# Codec.net
KiCad netlist of a schematic drawn in Altium Designer
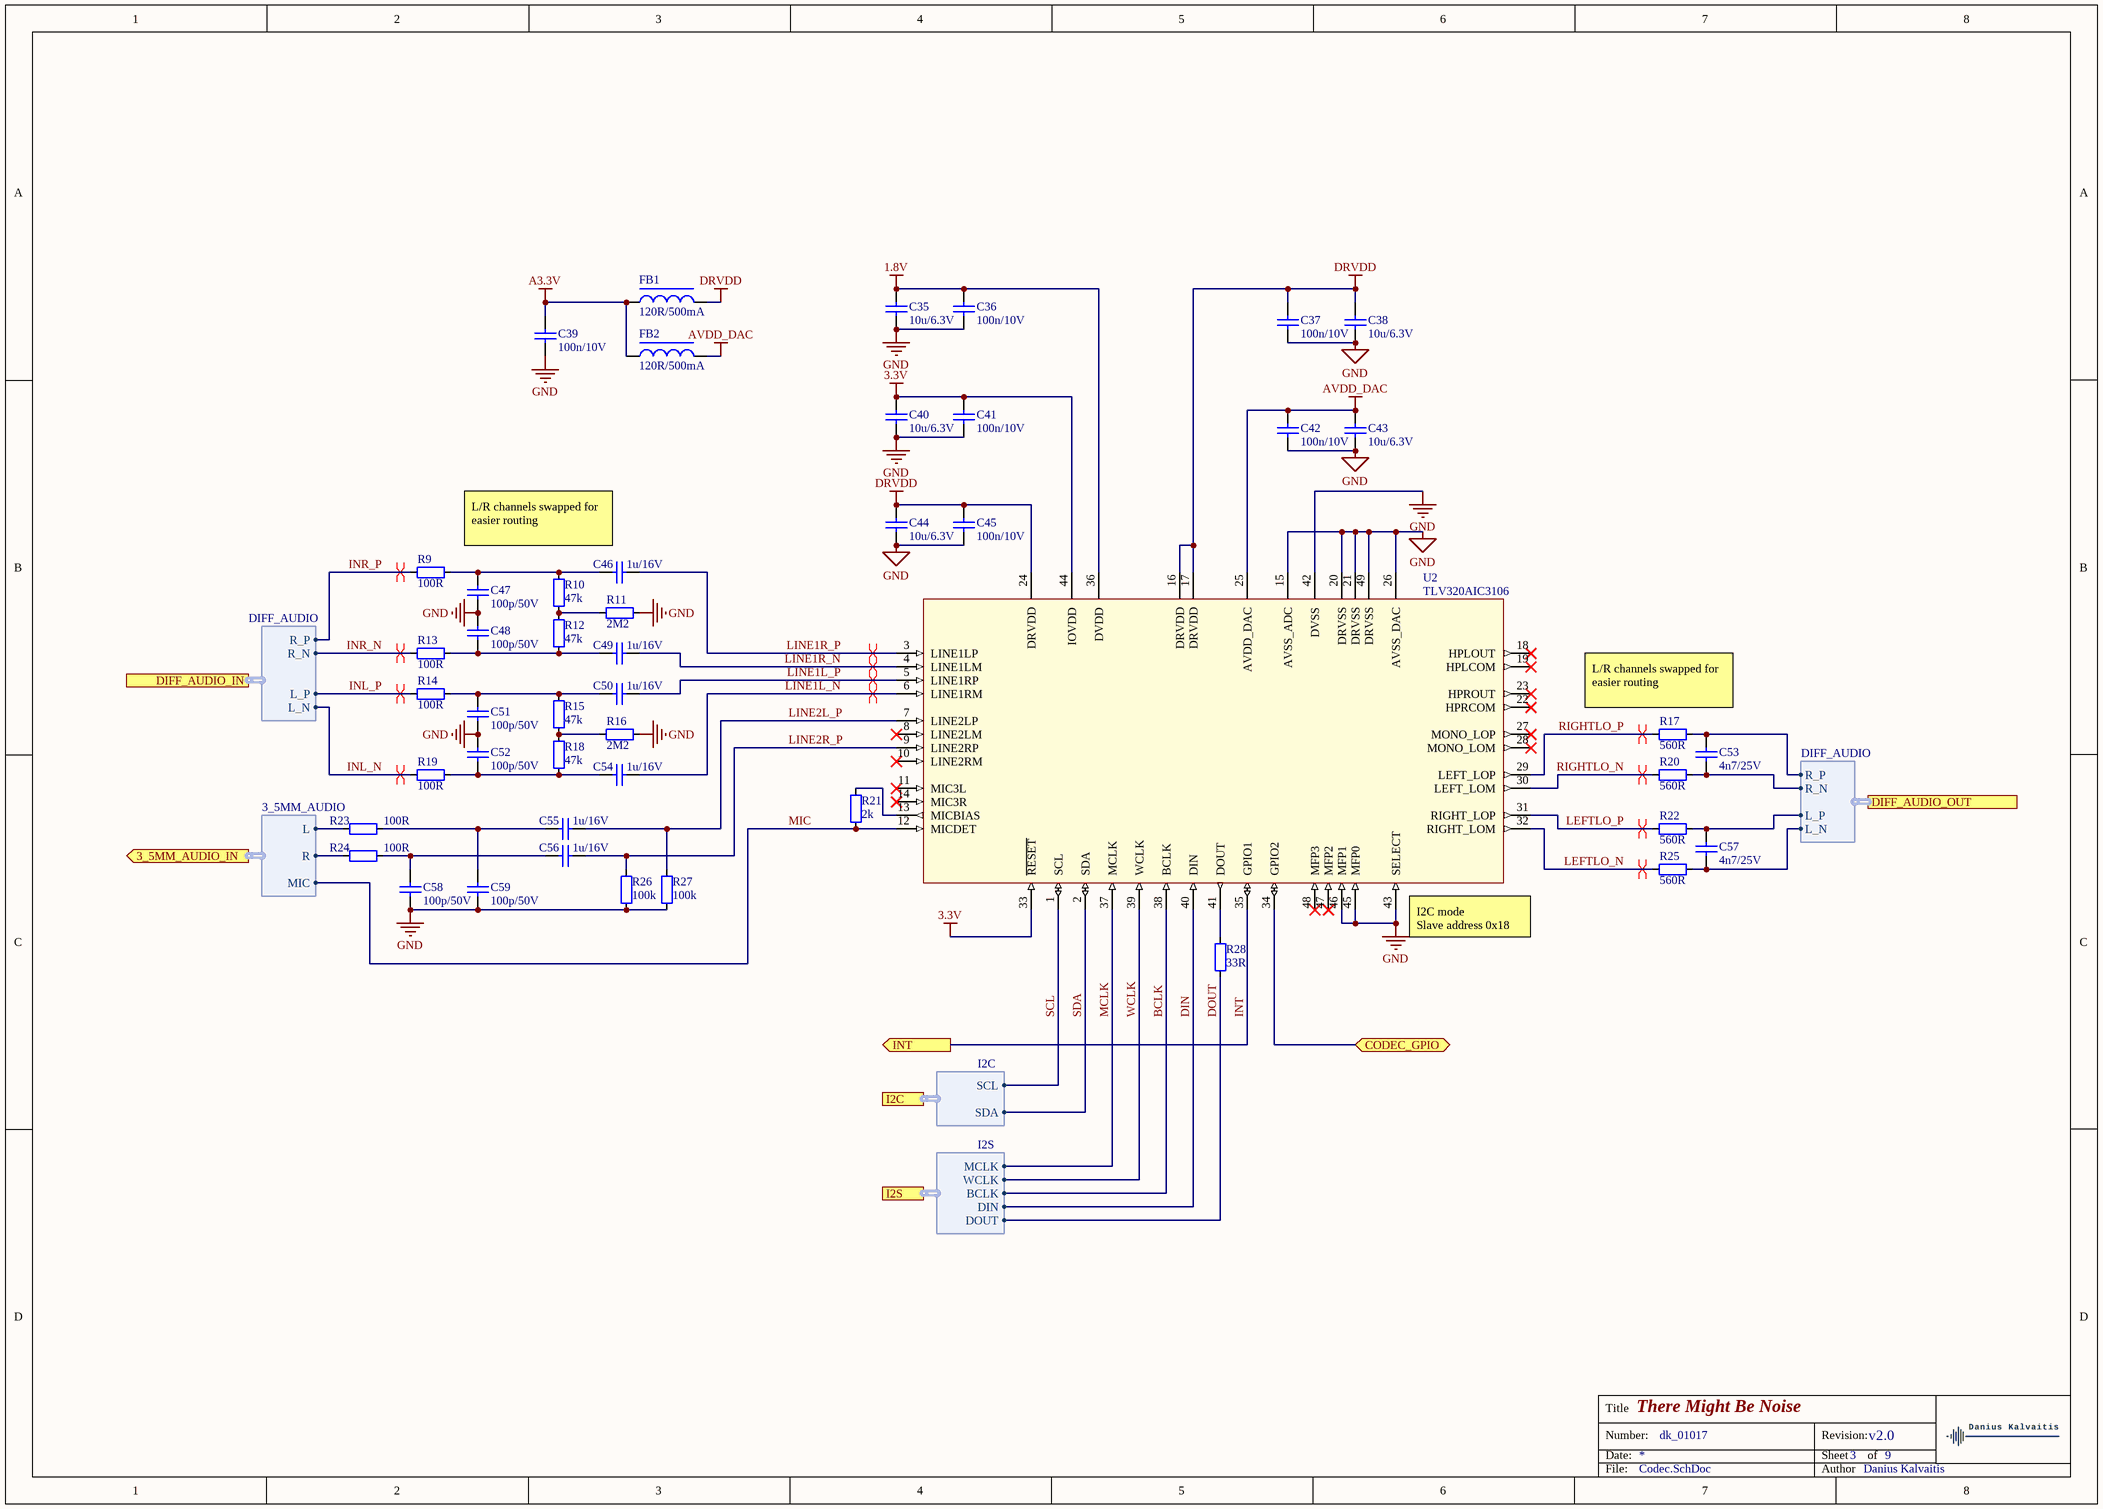
[diagram p0: Codec.SchDoc]

(export (version "E")
  (design (tool "Eeschema 10.0.6"))
  (components
    (comp (ref "C35")
      (value "10u/6.3V")
      (footprint "C0805")
      (fields (field (name "VOLTAGE") "6.3V") (field (name "TOLERANCE") "10%"))
      (libsource (lib "dk_capacitors") (part "10u 6V3 X7R 0805"))
    )
    (comp (ref "C36")
      (value "100n/10V")
      (footprint "C0402")
      (fields (field (name "VOLTAGE") "10V") (field (name "TOLERANCE") "20%"))
      (libsource (lib "dk_capacitors") (part "100n 10V X5R 0402"))
    )
    (comp (ref "C37")
      (value "100n/10V")
      (footprint "C0402")
      (fields (field (name "VOLTAGE") "10V") (field (name "TOLERANCE") "20%"))
      (libsource (lib "dk_capacitors") (part "100n 10V X5R 0402"))
    )
    (comp (ref "C38")
      (value "10u/6.3V")
      (footprint "C0805")
      (fields (field (name "VOLTAGE") "6.3V") (field (name "TOLERANCE") "10%"))
      (libsource (lib "dk_capacitors") (part "10u 6V3 X7R 0805"))
    )
    (comp (ref "C39")
      (value "100n/10V")
      (footprint "C0402")
      (fields (field (name "VOLTAGE") "10V") (field (name "TOLERANCE") "20%"))
      (libsource (lib "dk_capacitors") (part "100n 10V X5R 0402"))
    )
    (comp (ref "C40")
      (value "10u/6.3V")
      (footprint "C0805")
      (fields (field (name "VOLTAGE") "6.3V") (field (name "TOLERANCE") "10%"))
      (libsource (lib "dk_capacitors") (part "10u 6V3 X7R 0805"))
    )
    (comp (ref "C41")
      (value "100n/10V")
      (footprint "C0402")
      (fields (field (name "VOLTAGE") "10V") (field (name "TOLERANCE") "20%"))
      (libsource (lib "dk_capacitors") (part "100n 10V X5R 0402"))
    )
    (comp (ref "C42")
      (value "100n/10V")
      (footprint "C0402")
      (fields (field (name "VOLTAGE") "10V") (field (name "TOLERANCE") "20%"))
      (libsource (lib "dk_capacitors") (part "100n 10V X5R 0402"))
    )
    (comp (ref "C43")
      (value "10u/6.3V")
      (footprint "C0805")
      (fields (field (name "VOLTAGE") "6.3V") (field (name "TOLERANCE") "10%"))
      (libsource (lib "dk_capacitors") (part "10u 6V3 X7R 0805"))
    )
    (comp (ref "C44")
      (value "10u/6.3V")
      (footprint "C0805")
      (fields (field (name "VOLTAGE") "6.3V") (field (name "TOLERANCE") "10%"))
      (libsource (lib "dk_capacitors") (part "10u 6V3 X7R 0805"))
    )
    (comp (ref "C45")
      (value "100n/10V")
      (footprint "C0402")
      (fields (field (name "VOLTAGE") "10V") (field (name "TOLERANCE") "20%"))
      (libsource (lib "dk_capacitors") (part "100n 10V X5R 0402"))
    )
    (comp (ref "C46")
      (value "1u/16V")
      (footprint "C0603")
      (fields (field (name "VOLTAGE") "16V") (field (name "TOLERANCE") "10%"))
      (libsource (lib "dk_capacitors") (part "1u 16V X7R 0603"))
    )
    (comp (ref "C47")
      (value "100p/50V")
      (footprint "C0402")
      (fields (field (name "VOLTAGE") "50V") (field (name "TOLERANCE") "10%"))
      (libsource (lib "dk_capacitors") (part "100p 50V C0G 0402"))
    )
    (comp (ref "C48")
      (value "100p/50V")
      (footprint "C0402")
      (fields (field (name "VOLTAGE") "50V") (field (name "TOLERANCE") "10%"))
      (libsource (lib "dk_capacitors") (part "100p 50V C0G 0402"))
    )
    (comp (ref "C49")
      (value "1u/16V")
      (footprint "C0603")
      (fields (field (name "VOLTAGE") "16V") (field (name "TOLERANCE") "10%"))
      (libsource (lib "dk_capacitors") (part "1u 16V X7R 0603"))
    )
    (comp (ref "C50")
      (value "1u/16V")
      (footprint "C0603")
      (fields (field (name "VOLTAGE") "16V") (field (name "TOLERANCE") "10%"))
      (libsource (lib "dk_capacitors") (part "1u 16V X7R 0603"))
    )
    (comp (ref "C51")
      (value "100p/50V")
      (footprint "C0402")
      (fields (field (name "VOLTAGE") "50V") (field (name "TOLERANCE") "10%"))
      (libsource (lib "dk_capacitors") (part "100p 50V C0G 0402"))
    )
    (comp (ref "C52")
      (value "100p/50V")
      (footprint "C0402")
      (fields (field (name "VOLTAGE") "50V") (field (name "TOLERANCE") "10%"))
      (libsource (lib "dk_capacitors") (part "100p 50V C0G 0402"))
    )
    (comp (ref "C53")
      (value "4n7/25V")
      (footprint "C0402")
      (fields (field (name "VOLTAGE") "25V") (field (name "TOLERANCE") "10%"))
      (libsource (lib "dk_capacitors") (part "4n7 25V X7R 0402"))
    )
    (comp (ref "C54")
      (value "1u/16V")
      (footprint "C0603")
      (fields (field (name "VOLTAGE") "16V") (field (name "TOLERANCE") "10%"))
      (libsource (lib "dk_capacitors") (part "1u 16V X7R 0603"))
    )
    (comp (ref "C55")
      (value "1u/16V")
      (footprint "C0603")
      (fields (field (name "VOLTAGE") "16V") (field (name "TOLERANCE") "10%"))
      (libsource (lib "dk_capacitors") (part "1u 16V X7R 0603"))
    )
    (comp (ref "C56")
      (value "1u/16V")
      (footprint "C0603")
      (fields (field (name "VOLTAGE") "16V") (field (name "TOLERANCE") "10%"))
      (libsource (lib "dk_capacitors") (part "1u 16V X7R 0603"))
    )
    (comp (ref "C57")
      (value "4n7/25V")
      (footprint "C0402")
      (fields (field (name "VOLTAGE") "25V") (field (name "TOLERANCE") "10%"))
      (libsource (lib "dk_capacitors") (part "4n7 25V X7R 0402"))
    )
    (comp (ref "C58")
      (value "100p/50V")
      (footprint "C0402")
      (fields (field (name "VOLTAGE") "50V") (field (name "TOLERANCE") "10%"))
      (libsource (lib "dk_capacitors") (part "100p 50V C0G 0402"))
    )
    (comp (ref "C59")
      (value "100p/50V")
      (footprint "C0402")
      (fields (field (name "VOLTAGE") "50V") (field (name "TOLERANCE") "10%"))
      (libsource (lib "dk_capacitors") (part "100p 50V C0G 0402"))
    )
    (comp (ref "FB1")
      (value "120R/500mA")
      (footprint "FB0402")
      (description "120 Ohms @ 100MHz 1  Ferrite Bead 0402 (1005 Metric) 550mA 190mOhm")
      (fields (field (name "MANUFACTURER PART NUMBER") "BLM15AG121SN1D") (field (name "TOLERANCE") "25%"))
      (libsource (lib "dk_inductors") (part "BLM15AG121SN1D"))
    )
    (comp (ref "FB2")
      (value "120R/500mA")
      (footprint "FB0402")
      (description "120 Ohms @ 100MHz 1  Ferrite Bead 0402 (1005 Metric) 550mA 190mOhm")
      (fields (field (name "MANUFACTURER PART NUMBER") "BLM15AG121SN1D") (field (name "TOLERANCE") "25%"))
      (libsource (lib "dk_inductors") (part "BLM15AG121SN1D"))
    )
    (comp (ref "R9")
      (value "100R")
      (footprint "R0402")
      (fields (field (name "TOLERANCE") "1%") (field (name "VOLTAGE") "50V"))
      (libsource (lib "dk_resistors") (part "100R 63mW 50V 0402"))
    )
    (comp (ref "R10")
      (value "47k")
      (footprint "R0402")
      (fields (field (name "TOLERANCE") "1%") (field (name "VOLTAGE") "50V"))
      (libsource (lib "dk_resistors") (part "47k 63mW 50V 0402"))
    )
    (comp (ref "R11")
      (value "2M2")
      (footprint "R0402")
      (fields (field (name "TOLERANCE") "1%") (field (name "VOLTAGE") "50V"))
      (libsource (lib "dk_resistors") (part "2M2 63mW 50V 0402"))
    )
    (comp (ref "R12")
      (value "47k")
      (footprint "R0402")
      (fields (field (name "TOLERANCE") "1%") (field (name "VOLTAGE") "50V"))
      (libsource (lib "dk_resistors") (part "47k 63mW 50V 0402"))
    )
    (comp (ref "R13")
      (value "100R")
      (footprint "R0402")
      (fields (field (name "TOLERANCE") "1%") (field (name "VOLTAGE") "50V"))
      (libsource (lib "dk_resistors") (part "100R 63mW 50V 0402"))
    )
    (comp (ref "R14")
      (value "100R")
      (footprint "R0402")
      (fields (field (name "TOLERANCE") "1%") (field (name "VOLTAGE") "50V"))
      (libsource (lib "dk_resistors") (part "100R 63mW 50V 0402"))
    )
    (comp (ref "R15")
      (value "47k")
      (footprint "R0402")
      (fields (field (name "TOLERANCE") "1%") (field (name "VOLTAGE") "50V"))
      (libsource (lib "dk_resistors") (part "47k 63mW 50V 0402"))
    )
    (comp (ref "R16")
      (value "2M2")
      (footprint "R0402")
      (fields (field (name "TOLERANCE") "1%") (field (name "VOLTAGE") "50V"))
      (libsource (lib "dk_resistors") (part "2M2 63mW 50V 0402"))
    )
    (comp (ref "R17")
      (value "560R")
      (footprint "R0402")
      (fields (field (name "TOLERANCE") "0.5%") (field (name "VOLTAGE") "50V"))
      (libsource (lib "dk_resistors") (part "560R 63mW 50V 0402"))
    )
    (comp (ref "R18")
      (value "47k")
      (footprint "R0402")
      (fields (field (name "TOLERANCE") "1%") (field (name "VOLTAGE") "50V"))
      (libsource (lib "dk_resistors") (part "47k 63mW 50V 0402"))
    )
    (comp (ref "R19")
      (value "100R")
      (footprint "R0402")
      (fields (field (name "TOLERANCE") "1%") (field (name "VOLTAGE") "50V"))
      (libsource (lib "dk_resistors") (part "100R 63mW 50V 0402"))
    )
    (comp (ref "R20")
      (value "560R")
      (footprint "R0402")
      (fields (field (name "TOLERANCE") "0.5%") (field (name "VOLTAGE") "50V"))
      (libsource (lib "dk_resistors") (part "560R 63mW 50V 0402"))
    )
    (comp (ref "R21")
      (value "2k")
      (footprint "R0402")
      (fields (field (name "TOLERANCE") "1%") (field (name "VOLTAGE") "50V"))
      (libsource (lib "dk_resistors") (part "2k 63mW 50V 0402"))
    )
    (comp (ref "R22")
      (value "560R")
      (footprint "R0402")
      (fields (field (name "TOLERANCE") "0.5%") (field (name "VOLTAGE") "50V"))
      (libsource (lib "dk_resistors") (part "560R 63mW 50V 0402"))
    )
    (comp (ref "R23")
      (value "100R")
      (footprint "R0402")
      (fields (field (name "TOLERANCE") "1%") (field (name "VOLTAGE") "50V"))
      (libsource (lib "dk_resistors") (part "100R 63mW 50V 0402"))
    )
    (comp (ref "R24")
      (value "100R")
      (footprint "R0402")
      (fields (field (name "TOLERANCE") "1%") (field (name "VOLTAGE") "50V"))
      (libsource (lib "dk_resistors") (part "100R 63mW 50V 0402"))
    )
    (comp (ref "R25")
      (value "560R")
      (footprint "R0402")
      (fields (field (name "TOLERANCE") "0.5%") (field (name "VOLTAGE") "50V"))
      (libsource (lib "dk_resistors") (part "560R 63mW 50V 0402"))
    )
    (comp (ref "R26")
      (value "100k")
      (footprint "R0402")
      (fields (field (name "TOLERANCE") "1%") (field (name "VOLTAGE") "50V"))
      (libsource (lib "dk_resistors") (part "100k 63mW 50V 0402"))
    )
    (comp (ref "R27")
      (value "100k")
      (footprint "R0402")
      (fields (field (name "TOLERANCE") "1%") (field (name "VOLTAGE") "50V"))
      (libsource (lib "dk_resistors") (part "100k 63mW 50V 0402"))
    )
    (comp (ref "R28")
      (value "33R")
      (footprint "R0402")
      (fields (field (name "TOLERANCE") "5%") (field (name "VOLTAGE") "50V"))
      (libsource (lib "dk_resistors") (part "33R 63mW 50V 0402"))
    )
    (comp (ref "U2")
      (value "TLV320AIC3106")
      (footprint "VQFN-48")
      (description "TLV320AIC3106 Low-Power Stereo Audio CODEC for Portable Audio/Telephony")
      (fields (field (name "MANUFACTURER PART NUMBER") "TLV320AIC3106IRGZR"))
      (libsource (lib "dk_ic_audio") (part "TLV320AIC3106"))
    )
  )
  (nets
    (net (code "5") (name "/BCLK") (class "Default")
      (node (ref "U2") (pin "38") (pinfunction "BCLK_38") (pintype "input"))
    )
    (net (code "6") (name "/CODEC_GPIO") (class "Default")
      (node (ref "U2") (pin "34") (pinfunction "GPIO2_34") (pintype "bidirectional"))
    )
    (net (code "7") (name "/DIN") (class "Default")
      (node (ref "U2") (pin "40") (pinfunction "DIN_40") (pintype "input"))
    )
    (net (code "8") (name "/DOUT") (class "Default")
      (node (ref "R28") (pin "1") (pinfunction "1_1") (pintype "passive"))
    )
    (net (code "9") (name "/INL_N") (class "Default")
      (node (ref "R19") (pin "1") (pinfunction "1_1") (pintype "passive"))
    )
    (net (code "10") (name "/INL_P") (class "Default")
      (node (ref "R14") (pin "1") (pinfunction "1_1") (pintype "passive"))
    )
    (net (code "11") (name "/INR_N") (class "Default")
      (node (ref "R13") (pin "1") (pinfunction "1_1") (pintype "passive"))
    )
    (net (code "12") (name "/INR_P") (class "Default")
      (node (ref "R9") (pin "1") (pinfunction "1_1") (pintype "passive"))
    )
    (net (code "13") (name "/INT") (class "Default")
      (node (ref "U2") (pin "35") (pinfunction "GPIO1_35") (pintype "bidirectional"))
    )
    (net (code "14") (name "/L") (class "Default")
      (node (ref "R23") (pin "1") (pinfunction "1_1") (pintype "passive"))
    )
    (net (code "15") (name "/LEFTLO_N") (class "Default")
      (node (ref "R25") (pin "1") (pinfunction "1_1") (pintype "passive"))
      (node (ref "U2") (pin "32") (pinfunction "RIGHT_LOM_32") (pintype "output"))
    )
    (net (code "16") (name "/LEFTLO_P") (class "Default")
      (node (ref "R22") (pin "1") (pinfunction "1_1") (pintype "passive"))
      (node (ref "U2") (pin "31") (pinfunction "RIGHT_LOP_31") (pintype "output"))
    )
    (net (code "17") (name "/LINE1L_N") (class "Default")
      (node (ref "C54") (pin "1") (pinfunction "1_1") (pintype "passive"))
      (node (ref "U2") (pin "6") (pinfunction "LINE1RM_6") (pintype "input"))
    )
    (net (code "18") (name "/LINE1L_P") (class "Default")
      (node (ref "C50") (pin "1") (pinfunction "1_1") (pintype "passive"))
      (node (ref "U2") (pin "5") (pinfunction "LINE1RP_5") (pintype "input"))
    )
    (net (code "19") (name "/LINE1R_N") (class "Default")
      (node (ref "C49") (pin "1") (pinfunction "1_1") (pintype "passive"))
      (node (ref "U2") (pin "4") (pinfunction "LINE1LM_4") (pintype "input"))
    )
    (net (code "20") (name "/LINE1R_P") (class "Default")
      (node (ref "C46") (pin "1") (pinfunction "1_1") (pintype "passive"))
      (node (ref "U2") (pin "3") (pinfunction "LINE1LP_3") (pintype "input"))
    )
    (net (code "21") (name "/LINE2L_P") (class "Default")
      (node (ref "C55") (pin "1") (pinfunction "1_1") (pintype "passive"))
      (node (ref "R27") (pin "2") (pinfunction "2_2") (pintype "passive"))
      (node (ref "U2") (pin "7") (pinfunction "LINE2LP_7") (pintype "input"))
    )
    (net (code "22") (name "/LINE2R_P") (class "Default")
      (node (ref "C56") (pin "1") (pinfunction "1_1") (pintype "passive"))
      (node (ref "R26") (pin "2") (pinfunction "2_2") (pintype "passive"))
      (node (ref "U2") (pin "9") (pinfunction "LINE2RP_9") (pintype "input"))
    )
    (net (code "23") (name "/MCLK") (class "Default")
      (node (ref "U2") (pin "37") (pinfunction "MCLK_37") (pintype "input"))
    )
    (net (code "24") (name "/MIC") (class "Default")
      (node (ref "R21") (pin "1") (pinfunction "1_1") (pintype "passive"))
      (node (ref "U2") (pin "12") (pinfunction "MICDET_12") (pintype "input"))
    )
    (net (code "25") (name "/R") (class "Default")
      (node (ref "R24") (pin "1") (pinfunction "1_1") (pintype "passive"))
    )
    (net (code "26") (name "/RIGHTLO_N") (class "Default")
      (node (ref "R20") (pin "1") (pinfunction "1_1") (pintype "passive"))
      (node (ref "U2") (pin "30") (pinfunction "LEFT_LOM_30") (pintype "output"))
    )
    (net (code "27") (name "/RIGHTLO_P") (class "Default")
      (node (ref "R17") (pin "1") (pinfunction "1_1") (pintype "passive"))
      (node (ref "U2") (pin "29") (pinfunction "LEFT_LOP_29") (pintype "output"))
    )
    (net (code "28") (name "/SCL") (class "Default")
      (node (ref "U2") (pin "1") (pinfunction "SCL_1") (pintype "bidirectional"))
    )
    (net (code "29") (name "/SDA") (class "Default")
      (node (ref "U2") (pin "2") (pinfunction "SDA_2") (pintype "bidirectional"))
    )
    (net (code "30") (name "/WCLK") (class "Default")
      (node (ref "U2") (pin "39") (pinfunction "WCLK_39") (pintype "input"))
    )
    (net (code "35") (name "1.8V") (class "Default")
      (node (ref "C35") (pin "2") (pinfunction "2_2") (pintype "passive"))
      (node (ref "C36") (pin "2") (pinfunction "2_2") (pintype "passive"))
      (node (ref "U2") (pin "36") (pinfunction "DVDD_36") (pintype "power_in"))
    )
    (net (code "36") (name "3.3V") (class "Default")
      (node (ref "C40") (pin "2") (pinfunction "2_2") (pintype "passive"))
      (node (ref "C41") (pin "2") (pinfunction "2_2") (pintype "passive"))
      (node (ref "U2") (pin "33") (pinfunction "~{RESET}_33") (pintype "input"))
      (node (ref "U2") (pin "44") (pinfunction "IOVDD_44") (pintype "power_in"))
    )
    (net (code "37") (name "A3.3V") (class "Default")
      (node (ref "C39") (pin "2") (pinfunction "2_2") (pintype "passive"))
      (node (ref "FB1") (pin "1") (pinfunction "1_1") (pintype "passive"))
      (node (ref "FB2") (pin "1") (pinfunction "1_1") (pintype "passive"))
    )
    (net (code "38") (name "AVDD_DAC") (class "Default")
      (node (ref "C42") (pin "2") (pinfunction "2_2") (pintype "passive"))
      (node (ref "C43") (pin "2") (pinfunction "2_2") (pintype "passive"))
      (node (ref "FB2") (pin "2") (pinfunction "2_2") (pintype "passive"))
      (node (ref "U2") (pin "25") (pinfunction "AVDD_DAC_25") (pintype "power_in"))
    )
    (net (code "39") (name "DRVDD") (class "Default")
      (node (ref "C37") (pin "2") (pinfunction "2_2") (pintype "passive"))
      (node (ref "C38") (pin "2") (pinfunction "2_2") (pintype "passive"))
      (node (ref "C44") (pin "2") (pinfunction "2_2") (pintype "passive"))
      (node (ref "C45") (pin "2") (pinfunction "2_2") (pintype "passive"))
      (node (ref "FB1") (pin "2") (pinfunction "2_2") (pintype "passive"))
      (node (ref "U2") (pin "16") (pinfunction "DRVDD_16") (pintype "power_in"))
      (node (ref "U2") (pin "17") (pinfunction "DRVDD_17") (pintype "power_in"))
      (node (ref "U2") (pin "24") (pinfunction "DRVDD_24") (pintype "power_in"))
    )
    (net (code "40") (name "GND") (class "Default")
      (node (ref "C35") (pin "1") (pinfunction "1_1") (pintype "passive"))
      (node (ref "C36") (pin "1") (pinfunction "1_1") (pintype "passive"))
      (node (ref "C37") (pin "1") (pinfunction "1_1") (pintype "passive"))
      (node (ref "C38") (pin "1") (pinfunction "1_1") (pintype "passive"))
      (node (ref "C39") (pin "1") (pinfunction "1_1") (pintype "passive"))
      (node (ref "C40") (pin "1") (pinfunction "1_1") (pintype "passive"))
      (node (ref "C41") (pin "1") (pinfunction "1_1") (pintype "passive"))
      (node (ref "C42") (pin "1") (pinfunction "1_1") (pintype "passive"))
      (node (ref "C43") (pin "1") (pinfunction "1_1") (pintype "passive"))
      (node (ref "C44") (pin "1") (pinfunction "1_1") (pintype "passive"))
      (node (ref "C45") (pin "1") (pinfunction "1_1") (pintype "passive"))
      (node (ref "C47") (pin "1") (pinfunction "1_1") (pintype "passive"))
      (node (ref "C48") (pin "2") (pinfunction "2_2") (pintype "passive"))
      (node (ref "C51") (pin "1") (pinfunction "1_1") (pintype "passive"))
      (node (ref "C52") (pin "2") (pinfunction "2_2") (pintype "passive"))
      (node (ref "C58") (pin "1") (pinfunction "1_1") (pintype "passive"))
      (node (ref "C59") (pin "1") (pinfunction "1_1") (pintype "passive"))
      (node (ref "R11") (pin "2") (pinfunction "2_2") (pintype "passive"))
      (node (ref "R16") (pin "2") (pinfunction "2_2") (pintype "passive"))
      (node (ref "R26") (pin "1") (pinfunction "1_1") (pintype "passive"))
      (node (ref "R27") (pin "1") (pinfunction "1_1") (pintype "passive"))
      (node (ref "U2") (pin "15") (pinfunction "AVSS_ADC_15") (pintype "power_in"))
      (node (ref "U2") (pin "20") (pinfunction "DRVSS_20") (pintype "power_in"))
      (node (ref "U2") (pin "21") (pinfunction "DRVSS_21") (pintype "power_in"))
      (node (ref "U2") (pin "26") (pinfunction "AVSS_DAC_26") (pintype "power_in"))
      (node (ref "U2") (pin "42") (pinfunction "DVSS_42") (pintype "power_in"))
      (node (ref "U2") (pin "43") (pinfunction "SELECT_43") (pintype "input"))
      (node (ref "U2") (pin "45") (pinfunction "MFP0_45") (pintype "input"))
      (node (ref "U2") (pin "46") (pinfunction "MFP1_46") (pintype "input"))
      (node (ref "U2") (pin "49") (pinfunction "DRVSS_49") (pintype "power_in"))
    )
    (net (code "41") (name "Net-(C46-Pad2)") (class "Default")
      (node (ref "C46") (pin "2") (pinfunction "2_2") (pintype "passive"))
      (node (ref "C47") (pin "2") (pinfunction "2_2") (pintype "passive"))
      (node (ref "R10") (pin "2") (pinfunction "2_2") (pintype "passive"))
      (node (ref "R9") (pin "2") (pinfunction "2_2") (pintype "passive"))
    )
    (net (code "42") (name "Net-(C48-Pad1)") (class "Default")
      (node (ref "C48") (pin "1") (pinfunction "1_1") (pintype "passive"))
      (node (ref "C49") (pin "2") (pinfunction "2_2") (pintype "passive"))
      (node (ref "R12") (pin "1") (pinfunction "1_1") (pintype "passive"))
      (node (ref "R13") (pin "2") (pinfunction "2_2") (pintype "passive"))
    )
    (net (code "43") (name "Net-(C50-Pad2)") (class "Default")
      (node (ref "C50") (pin "2") (pinfunction "2_2") (pintype "passive"))
      (node (ref "C51") (pin "2") (pinfunction "2_2") (pintype "passive"))
      (node (ref "R14") (pin "2") (pinfunction "2_2") (pintype "passive"))
      (node (ref "R15") (pin "2") (pinfunction "2_2") (pintype "passive"))
    )
    (net (code "44") (name "Net-(C52-Pad1)") (class "Default")
      (node (ref "C52") (pin "1") (pinfunction "1_1") (pintype "passive"))
      (node (ref "C54") (pin "2") (pinfunction "2_2") (pintype "passive"))
      (node (ref "R18") (pin "1") (pinfunction "1_1") (pintype "passive"))
      (node (ref "R19") (pin "2") (pinfunction "2_2") (pintype "passive"))
    )
    (net (code "45") (name "Net-(C53-Pad1)") (class "Default")
      (node (ref "C53") (pin "1") (pinfunction "1_1") (pintype "passive"))
      (node (ref "R20") (pin "2") (pinfunction "2_2") (pintype "passive"))
    )
    (net (code "46") (name "Net-(C53-Pad2)") (class "Default")
      (node (ref "C53") (pin "2") (pinfunction "2_2") (pintype "passive"))
      (node (ref "R17") (pin "2") (pinfunction "2_2") (pintype "passive"))
    )
    (net (code "47") (name "Net-(C55-Pad2)") (class "Default")
      (node (ref "C55") (pin "2") (pinfunction "2_2") (pintype "passive"))
      (node (ref "C59") (pin "2") (pinfunction "2_2") (pintype "passive"))
      (node (ref "R23") (pin "2") (pinfunction "2_2") (pintype "passive"))
    )
    (net (code "48") (name "Net-(C56-Pad2)") (class "Default")
      (node (ref "C56") (pin "2") (pinfunction "2_2") (pintype "passive"))
      (node (ref "C58") (pin "2") (pinfunction "2_2") (pintype "passive"))
      (node (ref "R24") (pin "2") (pinfunction "2_2") (pintype "passive"))
    )
    (net (code "49") (name "Net-(C57-Pad1)") (class "Default")
      (node (ref "C57") (pin "1") (pinfunction "1_1") (pintype "passive"))
      (node (ref "R25") (pin "2") (pinfunction "2_2") (pintype "passive"))
    )
    (net (code "50") (name "Net-(C57-Pad2)") (class "Default")
      (node (ref "C57") (pin "2") (pinfunction "2_2") (pintype "passive"))
      (node (ref "R22") (pin "2") (pinfunction "2_2") (pintype "passive"))
    )
    (net (code "51") (name "Net-(R10-Pad1)") (class "Default")
      (node (ref "R10") (pin "1") (pinfunction "1_1") (pintype "passive"))
      (node (ref "R11") (pin "1") (pinfunction "1_1") (pintype "passive"))
      (node (ref "R12") (pin "2") (pinfunction "2_2") (pintype "passive"))
    )
    (net (code "52") (name "Net-(R15-Pad1)") (class "Default")
      (node (ref "R15") (pin "1") (pinfunction "1_1") (pintype "passive"))
      (node (ref "R16") (pin "1") (pinfunction "1_1") (pintype "passive"))
      (node (ref "R18") (pin "2") (pinfunction "2_2") (pintype "passive"))
    )
    (net (code "53") (name "Net-(U2-DOUT)") (class "Default")
      (node (ref "R28") (pin "2") (pinfunction "2_2") (pintype "passive"))
      (node (ref "U2") (pin "41") (pinfunction "DOUT_41") (pintype "output"))
    )
    (net (code "54") (name "Net-(U2-MICBIAS)") (class "Default")
      (node (ref "R21") (pin "2") (pinfunction "2_2") (pintype "passive"))
      (node (ref "U2") (pin "13") (pinfunction "MICBIAS_13") (pintype "output"))
    )
    (net (code "55") (name "unconnected-(U2-HPLCOM-Pad19)") (class "Default")
      (node (ref "U2") (pin "19") (pinfunction "HPLCOM_19") (pintype "output+no_connect"))
    )
    (net (code "56") (name "unconnected-(U2-HPLOUT-Pad18)") (class "Default")
      (node (ref "U2") (pin "18") (pinfunction "HPLOUT_18") (pintype "output+no_connect"))
    )
    (net (code "57") (name "unconnected-(U2-HPRCOM-Pad22)") (class "Default")
      (node (ref "U2") (pin "22") (pinfunction "HPRCOM_22") (pintype "output+no_connect"))
    )
    (net (code "58") (name "unconnected-(U2-HPROUT-Pad23)") (class "Default")
      (node (ref "U2") (pin "23") (pinfunction "HPROUT_23") (pintype "output+no_connect"))
    )
    (net (code "59") (name "unconnected-(U2-LINE2LM-Pad8)") (class "Default")
      (node (ref "U2") (pin "8") (pinfunction "LINE2LM_8") (pintype "input+no_connect"))
    )
    (net (code "60") (name "unconnected-(U2-LINE2RM-Pad10)") (class "Default")
      (node (ref "U2") (pin "10") (pinfunction "LINE2RM_10") (pintype "input+no_connect"))
    )
    (net (code "61") (name "unconnected-(U2-MFP2-Pad47)") (class "Default")
      (node (ref "U2") (pin "47") (pinfunction "MFP2_47") (pintype "input+no_connect"))
    )
    (net (code "62") (name "unconnected-(U2-MFP3-Pad48)") (class "Default")
      (node (ref "U2") (pin "48") (pinfunction "MFP3_48") (pintype "input+no_connect"))
    )
    (net (code "63") (name "unconnected-(U2-MIC3L-Pad11)") (class "Default")
      (node (ref "U2") (pin "11") (pinfunction "MIC3L_11") (pintype "input+no_connect"))
    )
    (net (code "64") (name "unconnected-(U2-MIC3R-Pad14)") (class "Default")
      (node (ref "U2") (pin "14") (pinfunction "MIC3R_14") (pintype "input+no_connect"))
    )
    (net (code "65") (name "unconnected-(U2-MONO_LOM-Pad28)") (class "Default")
      (node (ref "U2") (pin "28") (pinfunction "MONO_LOM_28") (pintype "output+no_connect"))
    )
    (net (code "66") (name "unconnected-(U2-MONO_LOP-Pad27)") (class "Default")
      (node (ref "U2") (pin "27") (pinfunction "MONO_LOP_27") (pintype "output+no_connect"))
    )
  )
)
